# Sheet1.net
KiCad netlist of a schematic drawn in Altium Designer
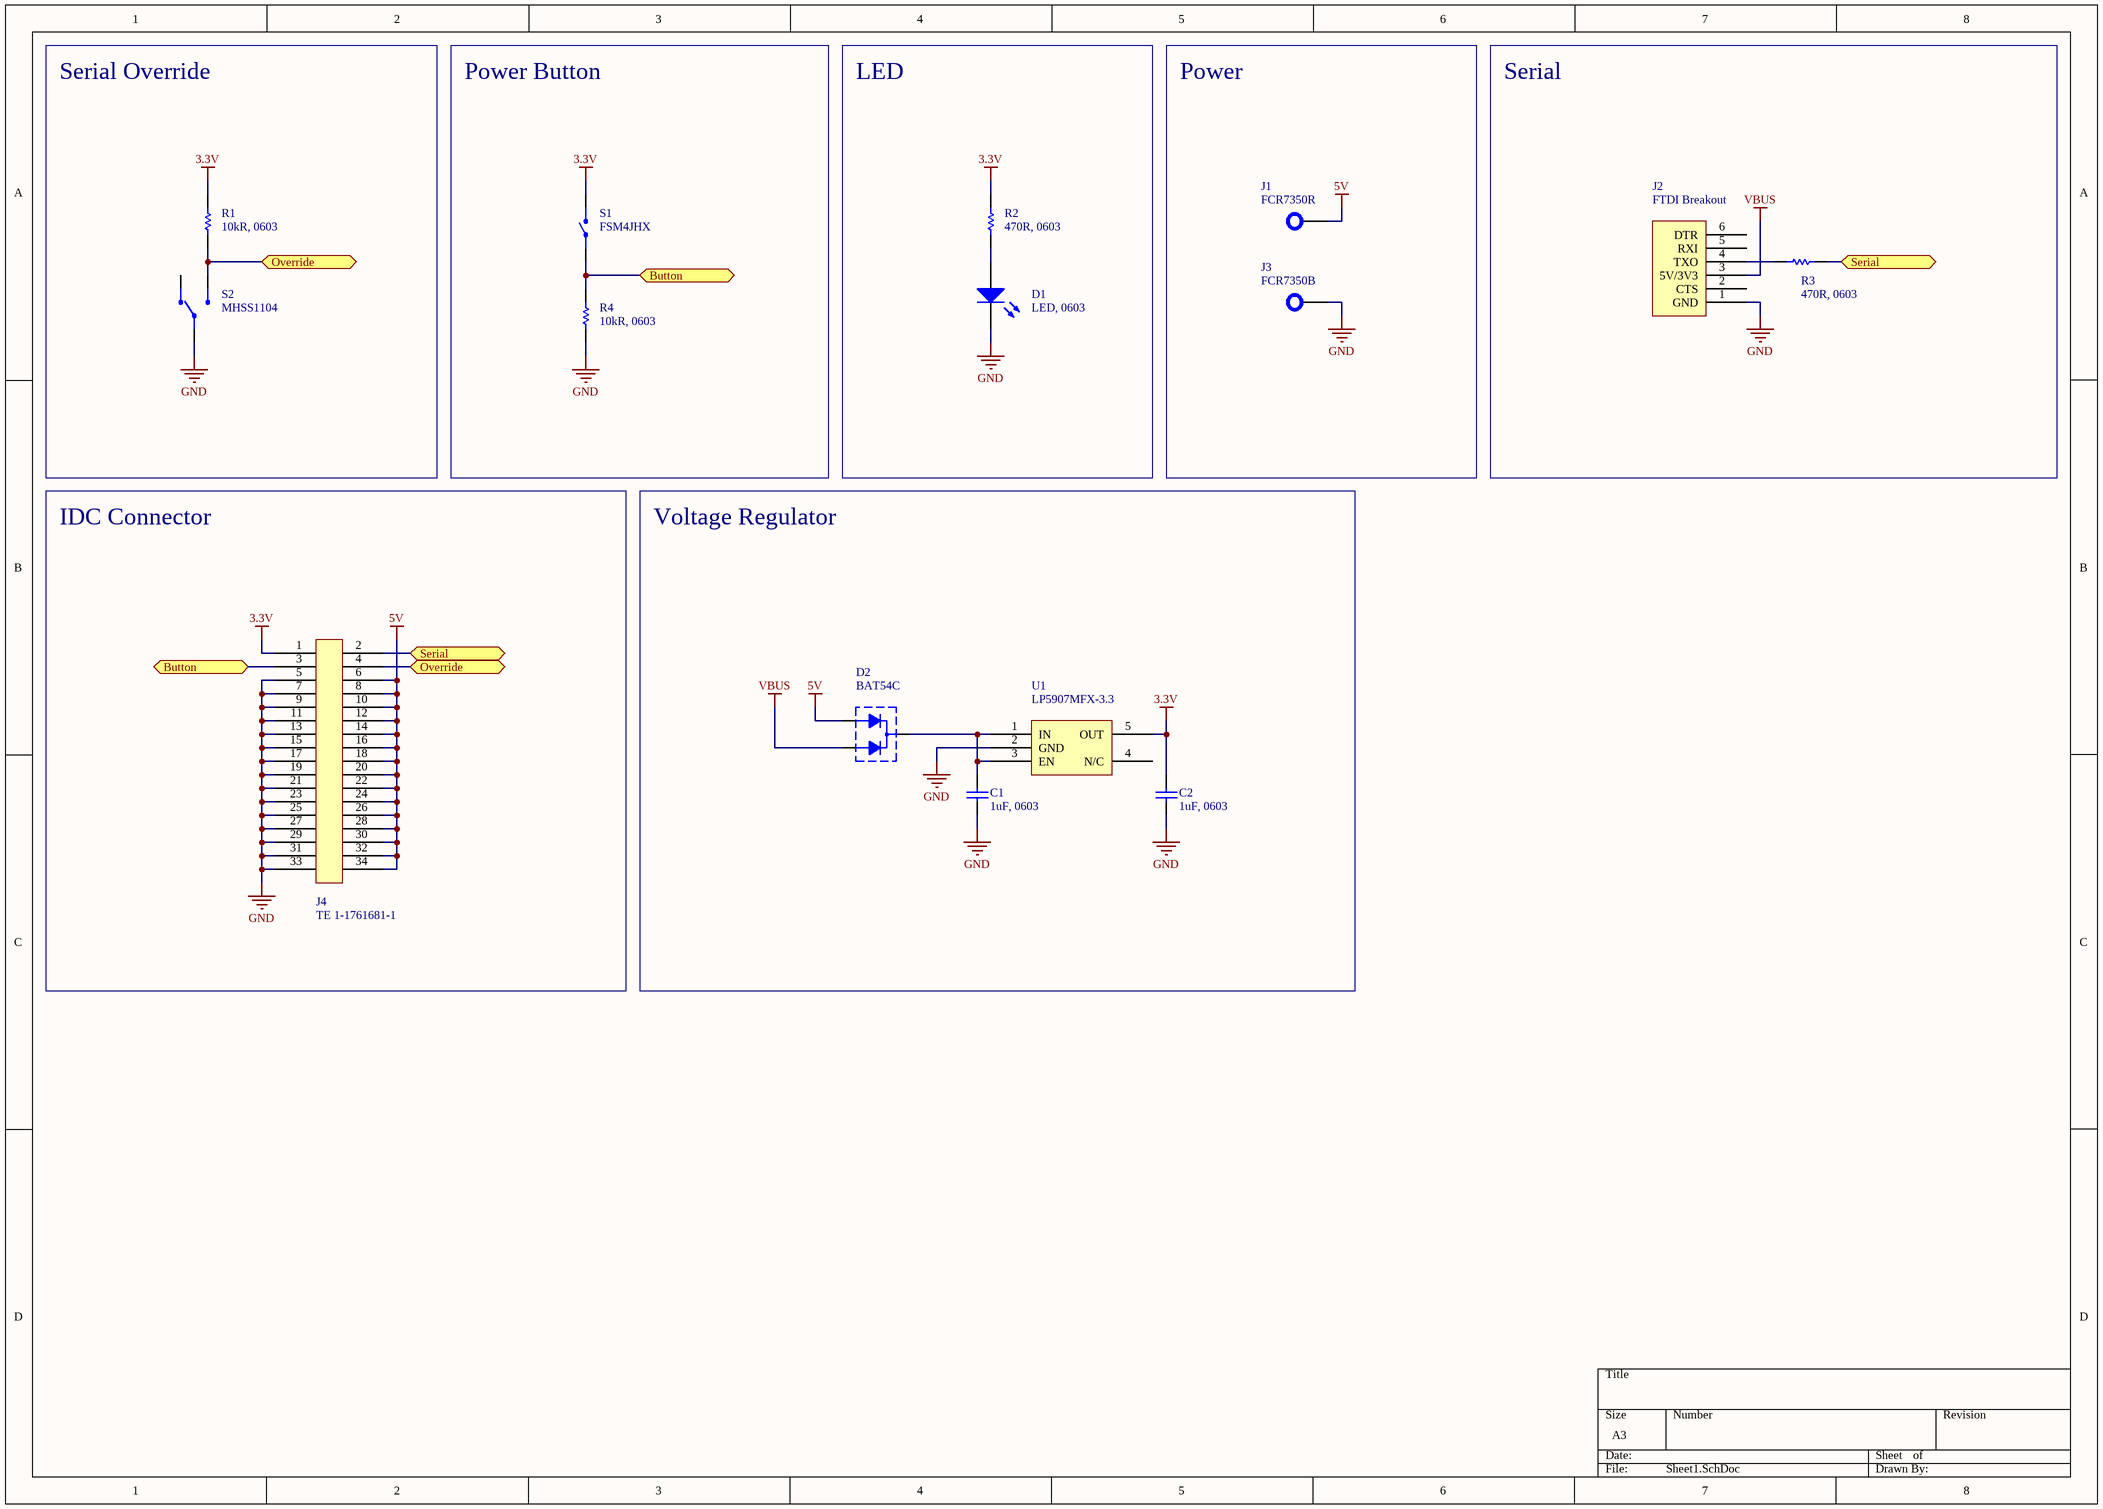
[diagram p0: Sheet1.SchDoc]

(export (version "E")
  (design (tool "Eeschema 10.0.6"))
  (components
    (comp (ref "C1")
      (value "1uF, 0603")
      (footprint "Capacitor 0603")
      (libsource (lib "x-io") (part "Capacitor"))
    )
    (comp (ref "C2")
      (value "1uF, 0603")
      (footprint "Capacitor 0603")
      (libsource (lib "x-io") (part "Capacitor"))
    )
    (comp (ref "D1") (value "LED, 0603") (footprint "LED 0603") (libsource (lib "x-io") (part "LED")))
    (comp (ref "D2") (value "BAT54C") (footprint "SOT-23") (libsource (lib "x-io") (part "BAT54C")))
    (comp (ref "J1") (value "FCR7350R") (footprint "FCR7350R") (libsource (lib "x-io") (part "FCR7350x")))
    (comp (ref "J2")
      (value "FTDI Breakout")
      (footprint "FTDI Breakout")
      (libsource (lib "x-io") (part "FTDI Breakout"))
    )
    (comp (ref "J3") (value "FCR7350B") (footprint "FCR7350B") (libsource (lib "x-io") (part "FCR7350x")))
    (comp (ref "J4")
      (value "TE 1-1761681-1")
      (footprint "TE 1-1761681-1")
      (libsource (lib "x-io") (part "TE 1-1761681-1"))
    )
    (comp (ref "R1")
      (value "10kR, 0603")
      (footprint "Resistor 0603")
      (libsource (lib "x-io") (part "Resistor"))
    )
    (comp (ref "R2")
      (value "470R, 0603")
      (footprint "Resistor 0603")
      (libsource (lib "x-io") (part "Resistor"))
    )
    (comp (ref "R3")
      (value "470R, 0603")
      (footprint "Resistor 0603")
      (libsource (lib "x-io") (part "Resistor"))
    )
    (comp (ref "R4")
      (value "10kR, 0603")
      (footprint "Resistor 0603")
      (libsource (lib "x-io") (part "Resistor"))
    )
    (comp (ref "S1") (value "FSM4JHX") (footprint "FSM4JHX") (libsource (lib "x-io") (part "Switch")))
    (comp (ref "S2") (value "MHSS1104") (footprint "MHSS1104") (libsource (lib "x-io") (part "Switch SPDT")))
    (comp (ref "U1")
      (value "LP5907MFX-3.3")
      (footprint "SOT-23-5")
      (libsource (lib "x-io") (part "LP5907MFX-3.3"))
    )
  )
  (nets
    (net (code "1") (name "/Button") (class "Default")
      (node (ref "J4") (pin "3") (pinfunction "3_3") (pintype "passive"))
      (node (ref "R4") (pin "2") (pinfunction "2_2") (pintype "passive"))
      (node (ref "S1") (pin "1") (pinfunction "1_1") (pintype "passive"))
    )
    (net (code "2") (name "/Override") (class "Default")
      (node (ref "J4") (pin "4") (pinfunction "4_4") (pintype "passive"))
      (node (ref "R1") (pin "1") (pinfunction "1_1") (pintype "passive"))
      (node (ref "S2") (pin "3") (pinfunction "3_3") (pintype "passive"))
    )
    (net (code "3") (name "/Serial") (class "Default")
      (node (ref "J4") (pin "2") (pinfunction "2_2") (pintype "passive"))
      (node (ref "R3") (pin "1") (pinfunction "1_1") (pintype "passive"))
    )
    (net (code "4") (name "3.3V") (class "Default")
      (node (ref "C2") (pin "2") (pinfunction "2_2") (pintype "passive"))
      (node (ref "J4") (pin "1") (pinfunction "*_1") (pintype "passive"))
      (node (ref "R1") (pin "2") (pinfunction "2_2") (pintype "passive"))
      (node (ref "R2") (pin "2") (pinfunction "2_2") (pintype "passive"))
      (node (ref "S1") (pin "2") (pinfunction "2_2") (pintype "passive"))
      (node (ref "U1") (pin "5") (pinfunction "OUT_5") (pintype "passive"))
    )
    (net (code "5") (name "5V") (class "Default")
      (node (ref "D2") (pin "2") (pinfunction "A2_2") (pintype "passive"))
      (node (ref "J1") (pin "Signal") (pinfunction "*_Signal") (pintype "passive"))
      (node (ref "J4") (pin "10") (pinfunction "10_10") (pintype "passive"))
      (node (ref "J4") (pin "12") (pinfunction "12_12") (pintype "passive"))
      (node (ref "J4") (pin "14") (pinfunction "14_14") (pintype "passive"))
      (node (ref "J4") (pin "16") (pinfunction "16_16") (pintype "passive"))
      (node (ref "J4") (pin "18") (pinfunction "18_18") (pintype "passive"))
      (node (ref "J4") (pin "20") (pinfunction "20_20") (pintype "passive"))
      (node (ref "J4") (pin "22") (pinfunction "22_22") (pintype "passive"))
      (node (ref "J4") (pin "24") (pinfunction "24_24") (pintype "passive"))
      (node (ref "J4") (pin "26") (pinfunction "26_26") (pintype "passive"))
      (node (ref "J4") (pin "28") (pinfunction "28_28") (pintype "passive"))
      (node (ref "J4") (pin "30") (pinfunction "30_30") (pintype "passive"))
      (node (ref "J4") (pin "32") (pinfunction "32_32") (pintype "passive"))
      (node (ref "J4") (pin "34") (pinfunction "34_34") (pintype "passive"))
      (node (ref "J4") (pin "6") (pinfunction "6_6") (pintype "passive"))
      (node (ref "J4") (pin "8") (pinfunction "8_8") (pintype "passive"))
    )
    (net (code "6") (name "GND") (class "Default")
      (node (ref "C1") (pin "1") (pinfunction "1_1") (pintype "passive"))
      (node (ref "C2") (pin "1") (pinfunction "1_1") (pintype "passive"))
      (node (ref "D1") (pin "K") (pinfunction "K_K") (pintype "passive"))
      (node (ref "J2") (pin "1") (pinfunction "GND_1") (pintype "passive"))
      (node (ref "J3") (pin "Signal") (pinfunction "*_Signal") (pintype "passive"))
      (node (ref "J4") (pin "11") (pinfunction "11_11") (pintype "passive"))
      (node (ref "J4") (pin "13") (pinfunction "13_13") (pintype "passive"))
      (node (ref "J4") (pin "15") (pinfunction "15_15") (pintype "passive"))
      (node (ref "J4") (pin "17") (pinfunction "17_17") (pintype "passive"))
      (node (ref "J4") (pin "19") (pinfunction "19_19") (pintype "passive"))
      (node (ref "J4") (pin "21") (pinfunction "21_21") (pintype "passive"))
      (node (ref "J4") (pin "23") (pinfunction "23_23") (pintype "passive"))
      (node (ref "J4") (pin "25") (pinfunction "25_25") (pintype "passive"))
      (node (ref "J4") (pin "27") (pinfunction "27_27") (pintype "passive"))
      (node (ref "J4") (pin "29") (pinfunction "29_29") (pintype "passive"))
      (node (ref "J4") (pin "31") (pinfunction "31_31") (pintype "passive"))
      (node (ref "J4") (pin "33") (pinfunction "33_33") (pintype "passive"))
      (node (ref "J4") (pin "5") (pinfunction "5_5") (pintype "passive"))
      (node (ref "J4") (pin "7") (pinfunction "7_7") (pintype "passive"))
      (node (ref "J4") (pin "9") (pinfunction "9_9") (pintype "passive"))
      (node (ref "R4") (pin "1") (pinfunction "1_1") (pintype "passive"))
      (node (ref "S2") (pin "2") (pinfunction "2_2") (pintype "passive"))
      (node (ref "U1") (pin "2") (pinfunction "GND_2") (pintype "passive"))
    )
    (net (code "7") (name "Net-(D1-PadA)") (class "Default")
      (node (ref "D1") (pin "A") (pinfunction "A_A") (pintype "passive"))
      (node (ref "R2") (pin "1") (pinfunction "1_1") (pintype "passive"))
    )
    (net (code "8") (name "Net-(D2-K)") (class "Default")
      (node (ref "C1") (pin "2") (pinfunction "2_2") (pintype "passive"))
      (node (ref "D2") (pin "3") (pinfunction "K_3") (pintype "passive"))
      (node (ref "U1") (pin "1") (pinfunction "IN_1") (pintype "passive"))
      (node (ref "U1") (pin "3") (pinfunction "EN_3") (pintype "passive"))
    )
    (net (code "9") (name "Net-(J2-TXO)") (class "Default")
      (node (ref "J2") (pin "4") (pinfunction "TXO_4") (pintype "passive"))
      (node (ref "R3") (pin "2") (pinfunction "2_2") (pintype "passive"))
    )
    (net (code "10") (name "VBUS") (class "Default")
      (node (ref "D2") (pin "1") (pinfunction "A1_1") (pintype "passive"))
      (node (ref "J2") (pin "3") (pinfunction "5V/3V3_3") (pintype "passive"))
    )
    (net (code "11") (name "unconnected-(J2-CTS-Pad2)") (class "Default")
      (node (ref "J2") (pin "2") (pinfunction "CTS_2") (pintype "passive"))
    )
    (net (code "12") (name "unconnected-(J2-DTR-Pad6)") (class "Default")
      (node (ref "J2") (pin "6") (pinfunction "DTR_6") (pintype "passive"))
    )
    (net (code "13") (name "unconnected-(J2-RXI-Pad5)") (class "Default")
      (node (ref "J2") (pin "5") (pinfunction "RXI_5") (pintype "passive"))
    )
    (net (code "14") (name "unconnected-(S2-Pad1)") (class "Default")
      (node (ref "S2") (pin "1") (pinfunction "1_1") (pintype "passive"))
    )
    (net (code "15") (name "unconnected-(U1-N{slash}C-Pad4)") (class "Default")
      (node (ref "U1") (pin "4") (pinfunction "N/C_4") (pintype "passive"))
    )
  )
)
